# FPV0_2_1.net
KiCad netlist of a schematic drawn in Altium Designer
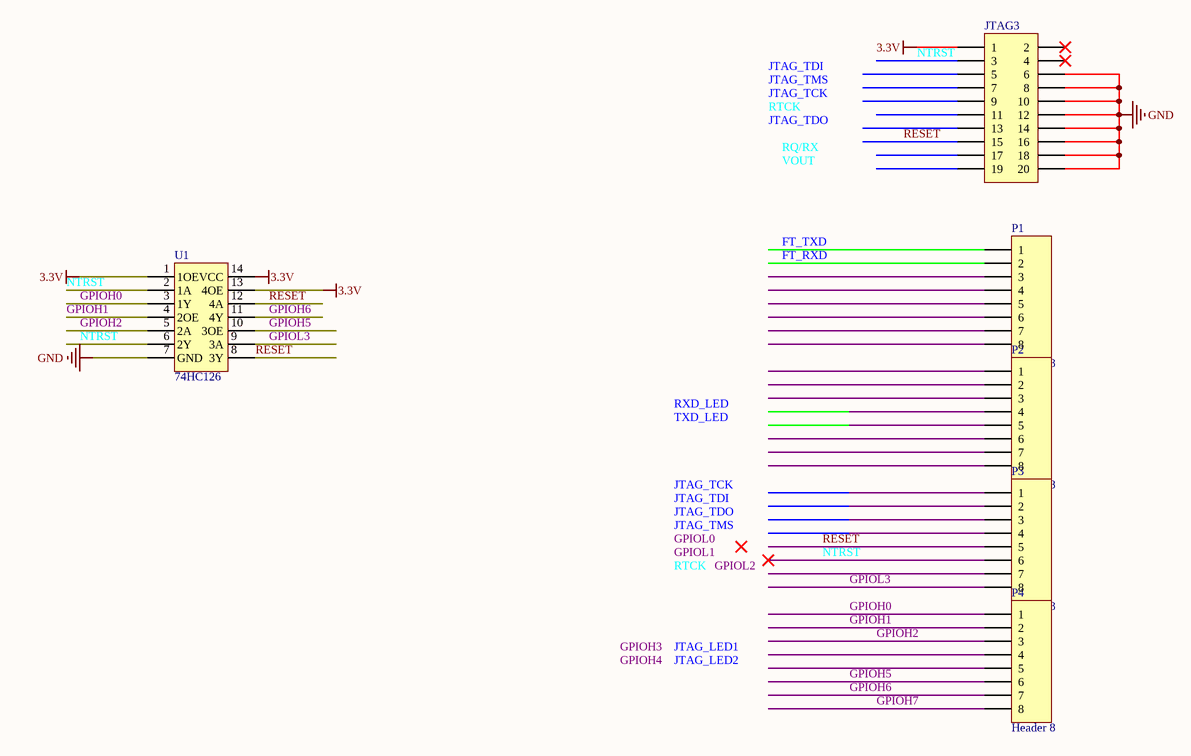
[diagram p0: FPV0.2.1.SchDoc]

(export (version "E")
  (design (tool "Eeschema 10.0.6"))
  (components
    (comp (ref "JTAG3")
      (value "Header 10X2")
      (footprint "HDR2X10")
      (description "Header, 10-Pin, Dual row")
      (fields (field (name "PUBLISHER") "Altium Limited"))
      (libsource (lib "Sparks") (part "Header 10X2"))
    )
    (comp (ref "P1")
      (value "Header 8")
      (footprint "HDR1X8")
      (description "Header, 8-Pin")
      (fields (field (name "PUBLISHER") "Altium Limited"))
      (libsource (lib "Sparks") (part "Header 8"))
    )
    (comp (ref "P2")
      (value "Header 8")
      (footprint "HDR1X8")
      (description "Header, 8-Pin")
      (fields (field (name "PUBLISHER") "Altium Limited"))
      (libsource (lib "Sparks") (part "Header 8"))
    )
    (comp (ref "P3")
      (value "Header 8")
      (footprint "HDR1X8")
      (description "Header, 8-Pin")
      (fields (field (name "PUBLISHER") "Altium Limited"))
      (libsource (lib "Sparks") (part "Header 8"))
    )
    (comp (ref "P4")
      (value "Header 8")
      (footprint "HDR1X8")
      (description "Header, 8-Pin")
      (fields (field (name "PUBLISHER") "Altium Limited"))
      (libsource (lib "Sparks") (part "Header 8"))
    )
    (comp (ref "U1")
      (value "74HC126")
      (footprint "SOP127P600-8N 74HC126")
      (libsource (lib "2号库") (part "74HC126"))
    )
  )
  (nets
    (net (code "1") (name "/FT_RXD") (class "Default")
      (node (ref "P1") (pin "2") (pinfunction "2_2") (pintype "passive"))
    )
    (net (code "2") (name "/FT_TXD") (class "Default")
      (node (ref "P1") (pin "1") (pinfunction "1_1") (pintype "passive"))
    )
    (net (code "3") (name "/GPIOH0") (class "Default")
      (node (ref "P4") (pin "1") (pinfunction "1_1") (pintype "passive"))
      (node (ref "U1") (pin "3") (pinfunction "1Y_3") (pintype "passive"))
    )
    (net (code "4") (name "/GPIOH1") (class "Default")
      (node (ref "P4") (pin "2") (pinfunction "2_2") (pintype "passive"))
      (node (ref "U1") (pin "4") (pinfunction "2OE_4") (pintype "passive"))
    )
    (net (code "5") (name "/GPIOH2") (class "Default")
      (node (ref "P4") (pin "3") (pinfunction "3_3") (pintype "passive"))
      (node (ref "U1") (pin "5") (pinfunction "2A_5") (pintype "passive"))
    )
    (net (code "8") (name "/GPIOH5") (class "Default")
      (node (ref "P4") (pin "6") (pinfunction "6_6") (pintype "passive"))
      (node (ref "U1") (pin "10") (pinfunction "3OE_10") (pintype "passive"))
    )
    (net (code "9") (name "/GPIOH6") (class "Default")
      (node (ref "P4") (pin "7") (pinfunction "7_7") (pintype "passive"))
      (node (ref "U1") (pin "11") (pinfunction "4Y_11") (pintype "passive"))
    )
    (net (code "10") (name "/GPIOH7") (class "Default")
      (node (ref "P4") (pin "8") (pinfunction "8_8") (pintype "passive"))
    )
    (net (code "14") (name "/GPIOL3") (class "Default")
      (node (ref "P3") (pin "8") (pinfunction "8_8") (pintype "passive"))
      (node (ref "U1") (pin "9") (pinfunction "3A_9") (pintype "passive"))
    )
    (net (code "21") (name "/NTRST") (class "Default")
      (node (ref "JTAG3") (pin "3") (pinfunction "3_3") (pintype "passive"))
      (node (ref "P3") (pin "6") (pinfunction "6_6") (pintype "passive"))
      (node (ref "U1") (pin "2") (pinfunction "1A_2") (pintype "passive"))
      (node (ref "U1") (pin "6") (pinfunction "2Y_6") (pintype "passive"))
    )
    (net (code "22") (name "/RESET") (class "Default")
      (node (ref "JTAG3") (pin "15") (pinfunction "15_15") (pintype "passive"))
      (node (ref "P3") (pin "5") (pinfunction "5_5") (pintype "passive"))
      (node (ref "U1") (pin "12") (pinfunction "4A_12") (pintype "passive"))
      (node (ref "U1") (pin "8") (pinfunction "3Y_8") (pintype "passive"))
    )
    (net (code "28") (name "3.3V") (class "Default")
      (node (ref "JTAG3") (pin "1") (pinfunction "1_1") (pintype "passive"))
      (node (ref "U1") (pin "1") (pinfunction "1OE_1") (pintype "passive"))
      (node (ref "U1") (pin "13") (pinfunction "4OE_13") (pintype "passive"))
      (node (ref "U1") (pin "14") (pinfunction "VCC_14") (pintype "passive"))
    )
    (net (code "29") (name "GND") (class "Default")
      (node (ref "JTAG3") (pin "10") (pinfunction "10_10") (pintype "passive"))
      (node (ref "JTAG3") (pin "12") (pinfunction "12_12") (pintype "passive"))
      (node (ref "JTAG3") (pin "14") (pinfunction "14_14") (pintype "passive"))
      (node (ref "JTAG3") (pin "16") (pinfunction "16_16") (pintype "passive"))
      (node (ref "JTAG3") (pin "18") (pinfunction "18_18") (pintype "passive"))
      (node (ref "JTAG3") (pin "20") (pinfunction "20_20") (pintype "passive"))
      (node (ref "JTAG3") (pin "6") (pinfunction "6_6") (pintype "passive"))
      (node (ref "JTAG3") (pin "8") (pinfunction "8_8") (pintype "passive"))
      (node (ref "U1") (pin "7") (pinfunction "GND_7") (pintype "passive"))
    )
    (net (code "30") (name "unconnected-(JTAG3-Pad2)") (class "Default")
      (node (ref "JTAG3") (pin "2") (pinfunction "2_2") (pintype "passive+no_connect"))
    )
    (net (code "31") (name "unconnected-(JTAG3-Pad4)") (class "Default")
      (node (ref "JTAG3") (pin "4") (pinfunction "4_4") (pintype "passive+no_connect"))
    )
    (net (code "32") (name "unconnected-(JTAG3-Pad5)") (class "Default")
      (node (ref "JTAG3") (pin "5") (pinfunction "5_5") (pintype "passive"))
    )
    (net (code "33") (name "unconnected-(JTAG3-Pad7)") (class "Default")
      (node (ref "JTAG3") (pin "7") (pinfunction "7_7") (pintype "passive"))
    )
    (net (code "34") (name "unconnected-(JTAG3-Pad9)") (class "Default")
      (node (ref "JTAG3") (pin "9") (pinfunction "9_9") (pintype "passive"))
    )
    (net (code "35") (name "unconnected-(JTAG3-Pad11)") (class "Default")
      (node (ref "JTAG3") (pin "11") (pinfunction "11_11") (pintype "passive"))
    )
    (net (code "36") (name "unconnected-(JTAG3-Pad13)") (class "Default")
      (node (ref "JTAG3") (pin "13") (pinfunction "13_13") (pintype "passive"))
    )
    (net (code "37") (name "unconnected-(JTAG3-Pad17)") (class "Default")
      (node (ref "JTAG3") (pin "17") (pinfunction "17_17") (pintype "passive"))
    )
    (net (code "38") (name "unconnected-(JTAG3-Pad19)") (class "Default")
      (node (ref "JTAG3") (pin "19") (pinfunction "19_19") (pintype "passive"))
    )
    (net (code "39") (name "unconnected-(P1-Pad3)") (class "Default")
      (node (ref "P1") (pin "3") (pinfunction "3_3") (pintype "passive"))
    )
    (net (code "40") (name "unconnected-(P1-Pad4)") (class "Default")
      (node (ref "P1") (pin "4") (pinfunction "4_4") (pintype "passive"))
    )
    (net (code "41") (name "unconnected-(P1-Pad5)") (class "Default")
      (node (ref "P1") (pin "5") (pinfunction "5_5") (pintype "passive"))
    )
    (net (code "42") (name "unconnected-(P1-Pad6)") (class "Default")
      (node (ref "P1") (pin "6") (pinfunction "6_6") (pintype "passive"))
    )
    (net (code "43") (name "unconnected-(P1-Pad7)") (class "Default")
      (node (ref "P1") (pin "7") (pinfunction "7_7") (pintype "passive"))
    )
    (net (code "44") (name "unconnected-(P1-Pad8)") (class "Default")
      (node (ref "P1") (pin "8") (pinfunction "8_8") (pintype "passive"))
    )
    (net (code "45") (name "unconnected-(P2-Pad1)") (class "Default")
      (node (ref "P2") (pin "1") (pinfunction "1_1") (pintype "passive"))
    )
    (net (code "46") (name "unconnected-(P2-Pad2)") (class "Default")
      (node (ref "P2") (pin "2") (pinfunction "2_2") (pintype "passive"))
    )
    (net (code "47") (name "unconnected-(P2-Pad3)") (class "Default")
      (node (ref "P2") (pin "3") (pinfunction "3_3") (pintype "passive"))
    )
    (net (code "48") (name "unconnected-(P2-Pad4)") (class "Default")
      (node (ref "P2") (pin "4") (pinfunction "4_4") (pintype "passive"))
    )
    (net (code "49") (name "unconnected-(P2-Pad5)") (class "Default")
      (node (ref "P2") (pin "5") (pinfunction "5_5") (pintype "passive"))
    )
    (net (code "50") (name "unconnected-(P2-Pad6)") (class "Default")
      (node (ref "P2") (pin "6") (pinfunction "6_6") (pintype "passive"))
    )
    (net (code "51") (name "unconnected-(P2-Pad7)") (class "Default")
      (node (ref "P2") (pin "7") (pinfunction "7_7") (pintype "passive"))
    )
    (net (code "52") (name "unconnected-(P2-Pad8)") (class "Default")
      (node (ref "P2") (pin "8") (pinfunction "8_8") (pintype "passive"))
    )
    (net (code "53") (name "unconnected-(P3-Pad1)") (class "Default")
      (node (ref "P3") (pin "1") (pinfunction "1_1") (pintype "passive"))
    )
    (net (code "54") (name "unconnected-(P3-Pad2)") (class "Default")
      (node (ref "P3") (pin "2") (pinfunction "2_2") (pintype "passive"))
    )
    (net (code "55") (name "unconnected-(P3-Pad3)") (class "Default")
      (node (ref "P3") (pin "3") (pinfunction "3_3") (pintype "passive"))
    )
    (net (code "56") (name "unconnected-(P3-Pad4)") (class "Default")
      (node (ref "P3") (pin "4") (pinfunction "4_4") (pintype "passive"))
    )
    (net (code "57") (name "unconnected-(P3-Pad7)") (class "Default")
      (node (ref "P3") (pin "7") (pinfunction "7_7") (pintype "passive"))
    )
    (net (code "58") (name "unconnected-(P4-Pad4)") (class "Default")
      (node (ref "P4") (pin "4") (pinfunction "4_4") (pintype "passive"))
    )
    (net (code "59") (name "unconnected-(P4-Pad5)") (class "Default")
      (node (ref "P4") (pin "5") (pinfunction "5_5") (pintype "passive"))
    )
  )
)
